# stm32f0driver1.net
KiCad netlist of a schematic drawn in EAGLE
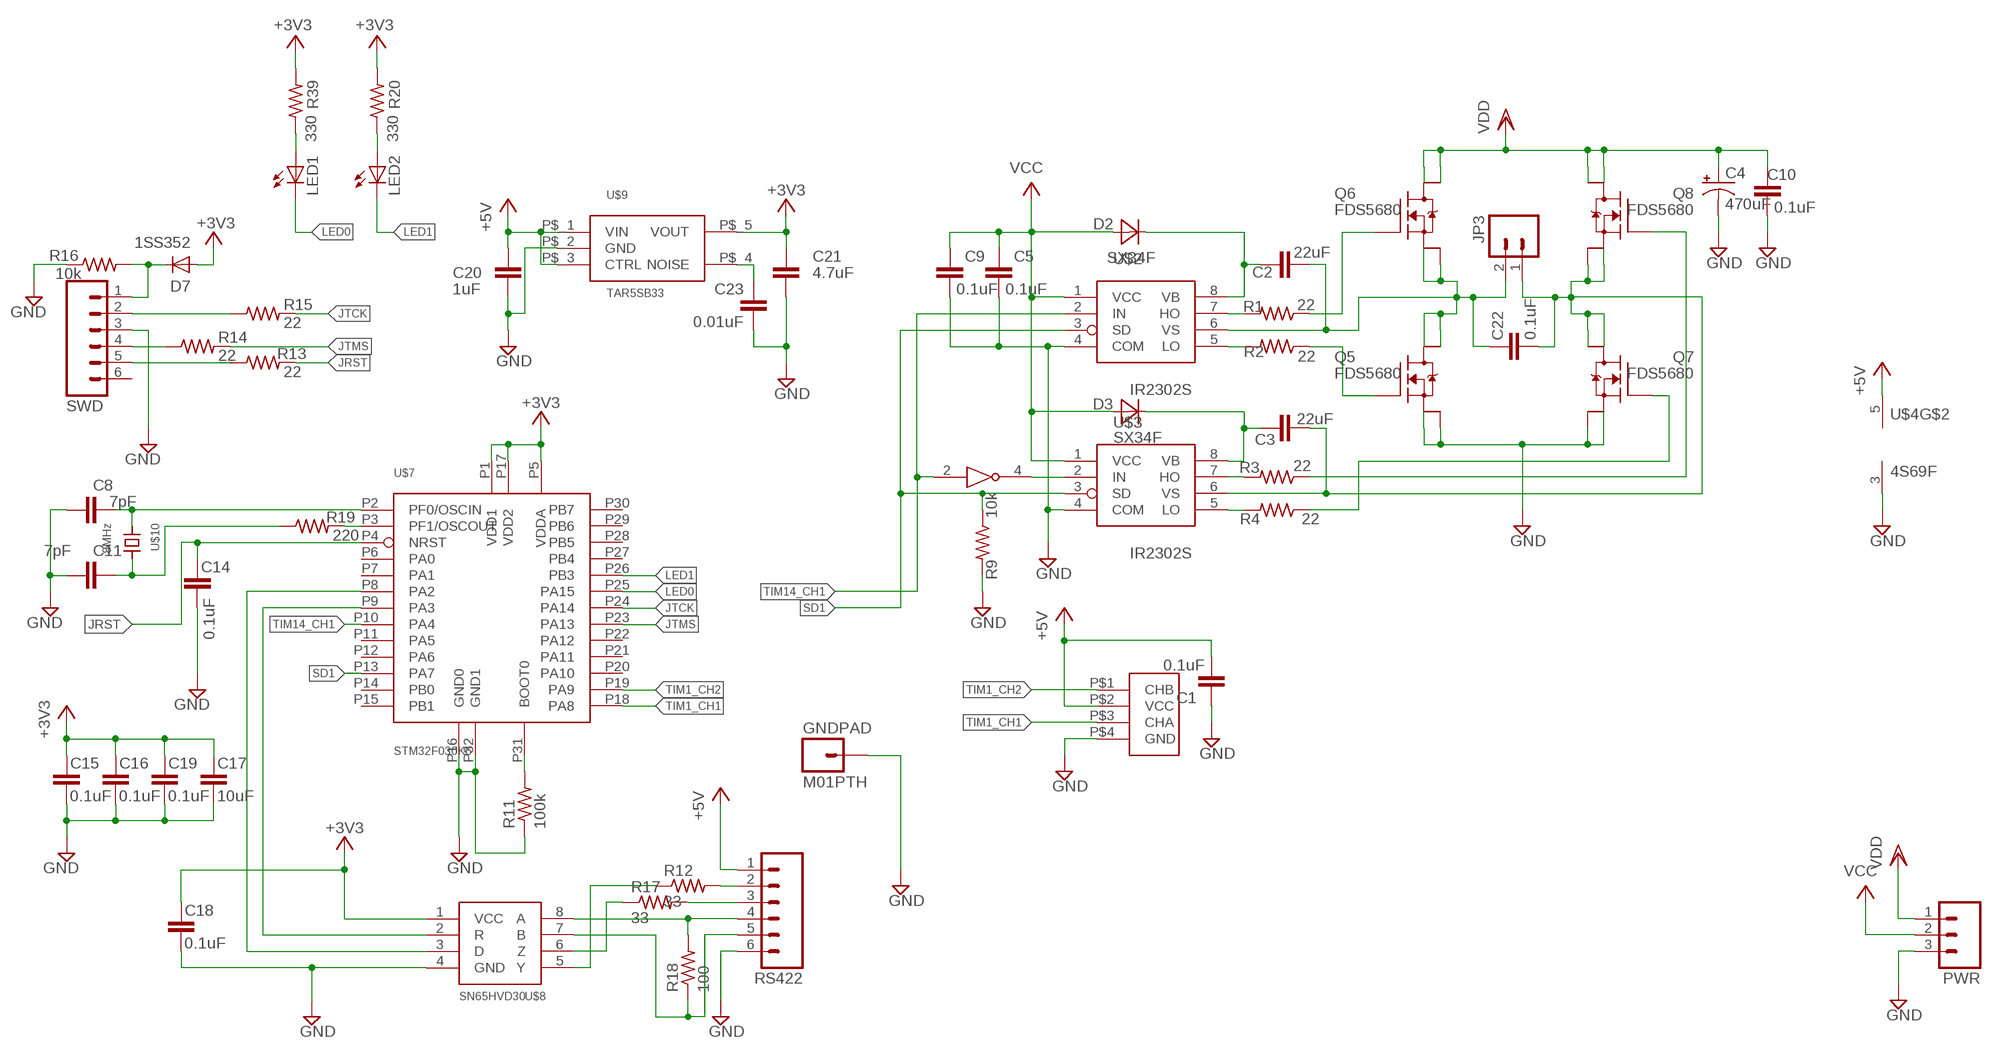
[diagram p0: schematic, sheet 1]

(export (version "E")
  (design (tool "Eeschema 10.0.6"))
  (components
    (comp (ref "C1")
      (value "0.1uF")
      (footprint "eagle-import:C0603")
      (libsource (lib "eagle-import") (part "C-EUC0603"))
    )
    (comp (ref "C2")
      (value "22uF")
      (footprint "eagle-import:C3225")
      (libsource (lib "eagle-import") (part "C-EUC3225"))
    )
    (comp (ref "C3")
      (value "22uF")
      (footprint "eagle-import:C3225")
      (libsource (lib "eagle-import") (part "C-EUC3225"))
    )
    (comp (ref "C4")
      (value "470uF")
      (footprint "eagle-import:E5-10,5")
      (libsource (lib "eagle-import") (part "CPOL-USE5-10.5"))
    )
    (comp (ref "C5")
      (value "0.1uF")
      (footprint "eagle-import:C0603")
      (libsource (lib "eagle-import") (part "C-EUC0603"))
    )
    (comp (ref "C8")
      (value "7pF")
      (footprint "eagle-import:C0603")
      (libsource (lib "eagle-import") (part "C-EUC0603"))
    )
    (comp (ref "C9")
      (value "0.1uF")
      (footprint "eagle-import:C0603")
      (libsource (lib "eagle-import") (part "C-EUC0603"))
    )
    (comp (ref "C10")
      (value "0.1uF")
      (footprint "eagle-import:C0603")
      (libsource (lib "eagle-import") (part "C-EUC0603"))
    )
    (comp (ref "C11")
      (value "7pF")
      (footprint "eagle-import:C0603")
      (libsource (lib "eagle-import") (part "C-EUC0603"))
    )
    (comp (ref "C14")
      (value "0.1uF")
      (footprint "eagle-import:C1608")
      (libsource (lib "eagle-import") (part "C-EUC1608"))
    )
    (comp (ref "C15")
      (value "0.1uF")
      (footprint "eagle-import:C1608")
      (libsource (lib "eagle-import") (part "C-EUC1608"))
    )
    (comp (ref "C16")
      (value "0.1uF")
      (footprint "eagle-import:C1608")
      (libsource (lib "eagle-import") (part "C-EUC1608"))
    )
    (comp (ref "C17")
      (value "10uF")
      (footprint "eagle-import:C3216")
      (libsource (lib "eagle-import") (part "C-EUC3216"))
    )
    (comp (ref "C18")
      (value "0.1uF")
      (footprint "eagle-import:C1608")
      (libsource (lib "eagle-import") (part "C-EUC1608"))
    )
    (comp (ref "C19")
      (value "0.1uF")
      (footprint "eagle-import:C1608")
      (libsource (lib "eagle-import") (part "C-EUC1608"))
    )
    (comp (ref "C20")
      (value "1uF")
      (footprint "eagle-import:C2012")
      (libsource (lib "eagle-import") (part "C-EUC2012"))
    )
    (comp (ref "C21")
      (value "4.7uF")
      (footprint "eagle-import:C2012")
      (libsource (lib "eagle-import") (part "C-EUC2012"))
    )
    (comp (ref "C22")
      (value "0.1uF")
      (footprint "eagle-import:C0603")
      (libsource (lib "eagle-import") (part "C-EUC0603"))
    )
    (comp (ref "C23")
      (value "0.01uF")
      (footprint "eagle-import:C0603")
      (libsource (lib "eagle-import") (part "C-EUC0603"))
    )
    (comp (ref "D2")
      (value "SX34F")
      (footprint "eagle-import:SMA")
      (libsource (lib "eagle-import") (part "MBRA340T3"))
    )
    (comp (ref "D3")
      (value "SX34F")
      (footprint "eagle-import:SMA")
      (libsource (lib "eagle-import") (part "MBRA340T3"))
    )
    (comp (ref "D7")
      (value "1SS352")
      (footprint "eagle-import:SOD-323")
      (libsource (lib "eagle-import") (part "DIODESOD"))
    )
    (comp (ref "GNDPAD")
      (value "M01PTH")
      (footprint "eagle-import:1X01")
      (libsource (lib "eagle-import") (part "M01PTH"))
    )
    (comp (ref "JP3")
      (value "M02PTH3")
      (footprint "eagle-import:1X02_LONGPADS")
      (libsource (lib "eagle-import") (part "M02PTH3"))
    )
    (comp (ref "LED1")
      (value "LED0603")
      (footprint "eagle-import:LED-0603")
      (libsource (lib "eagle-import") (part "LED0603"))
    )
    (comp (ref "LED2")
      (value "LED0603")
      (footprint "eagle-import:LED-0603")
      (libsource (lib "eagle-import") (part "LED0603"))
    )
    (comp (ref "PWR")
      (value "M03LONGPADS")
      (footprint "eagle-import:1X03_LONGPADS")
      (libsource (lib "eagle-import") (part "M03LONGPADS"))
    )
    (comp (ref "Q5")
      (value "FDS5680")
      (footprint "eagle-import:1206-8CHIP-FET")
      (libsource (lib "eagle-import") (part "FDS5680"))
    )
    (comp (ref "Q6")
      (value "FDS5680")
      (footprint "eagle-import:1206-8CHIP-FET")
      (libsource (lib "eagle-import") (part "FDS5680"))
    )
    (comp (ref "Q7")
      (value "FDS5680")
      (footprint "eagle-import:1206-8CHIP-FET")
      (libsource (lib "eagle-import") (part "FDS5680"))
    )
    (comp (ref "Q8")
      (value "FDS5680")
      (footprint "eagle-import:1206-8CHIP-FET")
      (libsource (lib "eagle-import") (part "FDS5680"))
    )
    (comp (ref "R1")
      (value "22")
      (footprint "eagle-import:R0603")
      (libsource (lib "eagle-import") (part "R-US_R0603"))
    )
    (comp (ref "R2")
      (value "22")
      (footprint "eagle-import:R0603")
      (libsource (lib "eagle-import") (part "R-US_R0603"))
    )
    (comp (ref "R3")
      (value "22")
      (footprint "eagle-import:R0603")
      (libsource (lib "eagle-import") (part "R-US_R0603"))
    )
    (comp (ref "R4")
      (value "22")
      (footprint "eagle-import:R0603")
      (libsource (lib "eagle-import") (part "R-US_R0603"))
    )
    (comp (ref "R9")
      (value "10k")
      (footprint "eagle-import:R0603")
      (libsource (lib "eagle-import") (part "R-US_R0603"))
    )
    (comp (ref "R11")
      (value "100k")
      (footprint "eagle-import:R0603")
      (libsource (lib "eagle-import") (part "R-US_R0603"))
    )
    (comp (ref "R12")
      (value "33")
      (footprint "eagle-import:R0603")
      (libsource (lib "eagle-import") (part "R-US_R0603"))
    )
    (comp (ref "R13")
      (value "22")
      (footprint "eagle-import:R0603")
      (libsource (lib "eagle-import") (part "R-US_R0603"))
    )
    (comp (ref "R14")
      (value "22")
      (footprint "eagle-import:R0603")
      (libsource (lib "eagle-import") (part "R-US_R0603"))
    )
    (comp (ref "R15")
      (value "22")
      (footprint "eagle-import:R0603")
      (libsource (lib "eagle-import") (part "R-US_R0603"))
    )
    (comp (ref "R16")
      (value "10k")
      (footprint "eagle-import:R0603")
      (libsource (lib "eagle-import") (part "R-US_R0603"))
    )
    (comp (ref "R17")
      (value "33")
      (footprint "eagle-import:R0603")
      (libsource (lib "eagle-import") (part "R-US_R0603"))
    )
    (comp (ref "R18")
      (value "100")
      (footprint "eagle-import:R0603")
      (libsource (lib "eagle-import") (part "R-US_R0603"))
    )
    (comp (ref "R19")
      (value "220")
      (footprint "eagle-import:R0603")
      (libsource (lib "eagle-import") (part "R-US_R0603"))
    )
    (comp (ref "R20")
      (value "330")
      (footprint "eagle-import:R0603")
      (libsource (lib "eagle-import") (part "R-US_R0603"))
    )
    (comp (ref "R39")
      (value "330")
      (footprint "eagle-import:R0603")
      (libsource (lib "eagle-import") (part "R-US_R0603"))
    )
    (comp (ref "RS422")
      (value "M06SIP")
      (footprint "eagle-import:1X06")
      (libsource (lib "eagle-import") (part "M06SIP"))
    )
    (comp (ref "SWD")
      (value "M06SIP")
      (footprint "eagle-import:1X06")
      (libsource (lib "eagle-import") (part "M06SIP"))
    )
    (comp (ref "U$1")
      (value "HEDS9701-C54")
      (footprint "eagle-import:HEDS9701")
      (libsource (lib "eagle-import") (part "HEDS9701-C54"))
    )
    (comp (ref "U$2")
      (value "IR2302S")
      (footprint "eagle-import:SO8")
      (libsource (lib "eagle-import") (part "IR2302S"))
    )
    (comp (ref "U$3")
      (value "IR2302S")
      (footprint "eagle-import:SO8")
      (libsource (lib "eagle-import") (part "IR2302S"))
    )
    (comp (ref "U$4")
      (value "4S69F")
      (footprint "eagle-import:SOT23-5")
      (libsource (lib "eagle-import") (part "4S69F"))
    )
    (comp (ref "U$7")
      (value "STM32F030K6")
      (footprint "eagle-import:LQFP32")
      (libsource (lib "eagle-import") (part "STM32F030K6"))
    )
    (comp (ref "U$8")
      (value "SN65HVD30")
      (footprint "eagle-import:SO8")
      (libsource (lib "eagle-import") (part "SN65HVD30"))
    )
    (comp (ref "U$9")
      (value "TAR5SB33")
      (footprint "eagle-import:TAR5SB33")
      (libsource (lib "eagle-import") (part "TAR5SB33"))
    )
    (comp (ref "U$10")
      (value "8MHz")
      (footprint "eagle-import:SMD5032")
      (libsource (lib "eagle-import") (part "NX5032GA"))
    )
  )
  (nets
    (net (code "1") (name "+3V3") (class "Default")
      (node (ref "C15") (pin "1") (pinfunction "1_1") (pintype "passive"))
      (node (ref "C16") (pin "1") (pinfunction "1_1") (pintype "passive"))
      (node (ref "C17") (pin "1") (pinfunction "1_1") (pintype "passive"))
      (node (ref "C18") (pin "1") (pinfunction "1_1") (pintype "passive"))
      (node (ref "C19") (pin "1") (pinfunction "1_1") (pintype "passive"))
      (node (ref "C21") (pin "1") (pinfunction "1_1") (pintype "passive"))
      (node (ref "D7") (pin "2") (pinfunction "A_2") (pintype "passive"))
      (node (ref "R20") (pin "2") (pinfunction "2_2") (pintype "passive"))
      (node (ref "R39") (pin "2") (pinfunction "2_2") (pintype "passive"))
      (node (ref "U$7") (pin "P1") (pinfunction "VDD1_P1") (pintype "power_in"))
      (node (ref "U$7") (pin "P17") (pinfunction "VDD2_P17") (pintype "bidirectional"))
      (node (ref "U$7") (pin "P5") (pinfunction "VDDA_P5") (pintype "power_in"))
      (node (ref "U$8") (pin "1") (pinfunction "VCC_1") (pintype "power_in"))
      (node (ref "U$9") (pin "P$_5") (pinfunction "VOUT_P$_5") (pintype "power_in"))
    )
    (net (code "2") (name "+5V") (class "Default")
      (node (ref "C1") (pin "2") (pinfunction "2_2") (pintype "passive"))
      (node (ref "C20") (pin "1") (pinfunction "1_1") (pintype "passive"))
      (node (ref "RS422") (pin "1") (pinfunction "1_1") (pintype "passive"))
      (node (ref "U$1") (pin "P$2") (pinfunction "VCC_P$2") (pintype "power_in"))
      (node (ref "U$4") (pin "5") (pinfunction "V+_5") (pintype "power_in"))
      (node (ref "U$9") (pin "P$_1") (pinfunction "VIN_P$_1") (pintype "power_in"))
      (node (ref "U$9") (pin "P$_3") (pinfunction "CTRL_P$_3") (pintype "input"))
    )
    (net (code "3") (name "GND") (class "Default")
      (node (ref "C1") (pin "1") (pinfunction "1_1") (pintype "passive"))
      (node (ref "C10") (pin "2") (pinfunction "2_2") (pintype "passive"))
      (node (ref "C11") (pin "2") (pinfunction "2_2") (pintype "passive"))
      (node (ref "C14") (pin "2") (pinfunction "2_2") (pintype "passive"))
      (node (ref "C15") (pin "2") (pinfunction "2_2") (pintype "passive"))
      (node (ref "C16") (pin "2") (pinfunction "2_2") (pintype "passive"))
      (node (ref "C17") (pin "2") (pinfunction "2_2") (pintype "passive"))
      (node (ref "C18") (pin "2") (pinfunction "2_2") (pintype "passive"))
      (node (ref "C19") (pin "2") (pinfunction "2_2") (pintype "passive"))
      (node (ref "C20") (pin "2") (pinfunction "2_2") (pintype "passive"))
      (node (ref "C21") (pin "2") (pinfunction "2_2") (pintype "passive"))
      (node (ref "C23") (pin "2") (pinfunction "2_2") (pintype "passive"))
      (node (ref "C4") (pin "-") (pinfunction "-_-") (pintype "passive"))
      (node (ref "C5") (pin "2") (pinfunction "2_2") (pintype "passive"))
      (node (ref "C8") (pin "2") (pinfunction "2_2") (pintype "passive"))
      (node (ref "C9") (pin "2") (pinfunction "2_2") (pintype "passive"))
      (node (ref "GNDPAD") (pin "1") (pinfunction "1_1") (pintype "passive"))
      (node (ref "PWR") (pin "3") (pinfunction "3_3") (pintype "passive"))
      (node (ref "Q5") (pin "1") (pinfunction "S_1") (pintype "passive"))
      (node (ref "Q5") (pin "2") (pinfunction "S1_2") (pintype "passive"))
      (node (ref "Q5") (pin "3") (pinfunction "S2_3") (pintype "passive"))
      (node (ref "Q7") (pin "1") (pinfunction "S_1") (pintype "passive"))
      (node (ref "Q7") (pin "2") (pinfunction "S1_2") (pintype "passive"))
      (node (ref "Q7") (pin "3") (pinfunction "S2_3") (pintype "passive"))
      (node (ref "R11") (pin "1") (pinfunction "1_1") (pintype "passive"))
      (node (ref "R16") (pin "1") (pinfunction "1_1") (pintype "passive"))
      (node (ref "R9") (pin "2") (pinfunction "2_2") (pintype "passive"))
      (node (ref "RS422") (pin "6") (pinfunction "6_6") (pintype "passive"))
      (node (ref "SWD") (pin "3") (pinfunction "3_3") (pintype "passive"))
      (node (ref "U$1") (pin "P$4") (pinfunction "GND_P$4") (pintype "power_in"))
      (node (ref "U$2") (pin "4") (pinfunction "COM_4") (pintype "power_in"))
      (node (ref "U$3") (pin "4") (pinfunction "COM_4") (pintype "power_in"))
      (node (ref "U$4") (pin "3") (pinfunction "V-_3") (pintype "power_in"))
      (node (ref "U$7") (pin "P16") (pinfunction "GND0_P16") (pintype "power_in"))
      (node (ref "U$7") (pin "P32") (pinfunction "GND1_P32") (pintype "bidirectional"))
      (node (ref "U$8") (pin "4") (pinfunction "GND_4") (pintype "power_in"))
      (node (ref "U$9") (pin "P$_2") (pinfunction "GND_P$_2") (pintype "power_in"))
    )
    (net (code "4") (name "JRST") (class "Default")
      (node (ref "C14") (pin "1") (pinfunction "1_1") (pintype "passive"))
      (node (ref "R13") (pin "2") (pinfunction "2_2") (pintype "passive"))
      (node (ref "U$7") (pin "P4") (pinfunction "NRST_P4") (pintype "input"))
    )
    (net (code "5") (name "JTCK") (class "Default")
      (node (ref "R15") (pin "2") (pinfunction "2_2") (pintype "passive"))
      (node (ref "U$7") (pin "P24") (pinfunction "PA14_P24") (pintype "bidirectional"))
    )
    (net (code "6") (name "JTMS") (class "Default")
      (node (ref "R14") (pin "2") (pinfunction "2_2") (pintype "passive"))
      (node (ref "U$7") (pin "P23") (pinfunction "PA13_P23") (pintype "bidirectional"))
    )
    (net (code "7") (name "LED0") (class "Default")
      (node (ref "LED1") (pin "C") (pinfunction "C_C") (pintype "passive"))
      (node (ref "U$7") (pin "P25") (pinfunction "PA15_P25") (pintype "bidirectional"))
    )
    (net (code "8") (name "LED1") (class "Default")
      (node (ref "LED2") (pin "C") (pinfunction "C_C") (pintype "passive"))
      (node (ref "U$7") (pin "P26") (pinfunction "PB3_P26") (pintype "bidirectional"))
    )
    (net (code "9") (name "Net-(D7-C)") (class "Default")
      (node (ref "D7") (pin "1") (pinfunction "C_1") (pintype "passive"))
      (node (ref "R16") (pin "2") (pinfunction "2_2") (pintype "passive"))
      (node (ref "SWD") (pin "1") (pinfunction "1_1") (pintype "passive"))
    )
    (net (code "10") (name "Net-(LED1-PadA)") (class "Default")
      (node (ref "LED1") (pin "A") (pinfunction "A_A") (pintype "passive"))
      (node (ref "R39") (pin "1") (pinfunction "1_1") (pintype "passive"))
    )
    (net (code "11") (name "Net-(LED2-PadA)") (class "Default")
      (node (ref "LED2") (pin "A") (pinfunction "A_A") (pintype "passive"))
      (node (ref "R20") (pin "1") (pinfunction "1_1") (pintype "passive"))
    )
    (net (code "12") (name "Net-(Q5-D)") (class "Default")
      (node (ref "C2") (pin "2") (pinfunction "2_2") (pintype "passive"))
      (node (ref "C22") (pin "1") (pinfunction "1_1") (pintype "passive"))
      (node (ref "JP3") (pin "2") (pinfunction "2_2") (pintype "passive"))
      (node (ref "Q5") (pin "5") (pinfunction "D_5") (pintype "passive"))
      (node (ref "Q5") (pin "6") (pinfunction "D1_6") (pintype "passive"))
      (node (ref "Q5") (pin "7") (pinfunction "D2_7") (pintype "passive"))
      (node (ref "Q5") (pin "8") (pinfunction "D3_8") (pintype "passive"))
      (node (ref "Q6") (pin "1") (pinfunction "S_1") (pintype "passive"))
      (node (ref "Q6") (pin "2") (pinfunction "S1_2") (pintype "passive"))
      (node (ref "Q6") (pin "3") (pinfunction "S2_3") (pintype "passive"))
      (node (ref "U$2") (pin "6") (pinfunction "VS_6") (pintype "bidirectional"))
    )
    (net (code "13") (name "Net-(Q5-G)") (class "Default")
      (node (ref "Q5") (pin "4") (pinfunction "G_4") (pintype "passive"))
      (node (ref "R2") (pin "1") (pinfunction "1_1") (pintype "passive"))
    )
    (net (code "14") (name "Net-(Q6-G)") (class "Default")
      (node (ref "Q6") (pin "4") (pinfunction "G_4") (pintype "passive"))
      (node (ref "R1") (pin "1") (pinfunction "1_1") (pintype "passive"))
    )
    (net (code "15") (name "Net-(Q7-D)") (class "Default")
      (node (ref "C22") (pin "2") (pinfunction "2_2") (pintype "passive"))
      (node (ref "C3") (pin "2") (pinfunction "2_2") (pintype "passive"))
      (node (ref "JP3") (pin "1") (pinfunction "1_1") (pintype "passive"))
      (node (ref "Q7") (pin "5") (pinfunction "D_5") (pintype "passive"))
      (node (ref "Q7") (pin "6") (pinfunction "D1_6") (pintype "passive"))
      (node (ref "Q7") (pin "7") (pinfunction "D2_7") (pintype "passive"))
      (node (ref "Q7") (pin "8") (pinfunction "D3_8") (pintype "passive"))
      (node (ref "Q8") (pin "1") (pinfunction "S_1") (pintype "passive"))
      (node (ref "Q8") (pin "2") (pinfunction "S1_2") (pintype "passive"))
      (node (ref "Q8") (pin "3") (pinfunction "S2_3") (pintype "passive"))
      (node (ref "U$3") (pin "6") (pinfunction "VS_6") (pintype "bidirectional"))
    )
    (net (code "16") (name "Net-(Q7-G)") (class "Default")
      (node (ref "Q7") (pin "4") (pinfunction "G_4") (pintype "passive"))
      (node (ref "R4") (pin "1") (pinfunction "1_1") (pintype "passive"))
    )
    (net (code "17") (name "Net-(Q8-G)") (class "Default")
      (node (ref "Q8") (pin "4") (pinfunction "G_4") (pintype "passive"))
      (node (ref "R3") (pin "1") (pinfunction "1_1") (pintype "passive"))
    )
    (net (code "18") (name "Net-(R12-Pad2)") (class "Default")
      (node (ref "R12") (pin "2") (pinfunction "2_2") (pintype "passive"))
      (node (ref "RS422") (pin "2") (pinfunction "2_2") (pintype "passive"))
    )
    (net (code "19") (name "Net-(R13-Pad1)") (class "Default")
      (node (ref "R13") (pin "1") (pinfunction "1_1") (pintype "passive"))
      (node (ref "SWD") (pin "5") (pinfunction "5_5") (pintype "passive"))
    )
    (net (code "20") (name "Net-(R14-Pad1)") (class "Default")
      (node (ref "R14") (pin "1") (pinfunction "1_1") (pintype "passive"))
      (node (ref "SWD") (pin "4") (pinfunction "4_4") (pintype "passive"))
    )
    (net (code "21") (name "Net-(R15-Pad1)") (class "Default")
      (node (ref "R15") (pin "1") (pinfunction "1_1") (pintype "passive"))
      (node (ref "SWD") (pin "2") (pinfunction "2_2") (pintype "passive"))
    )
    (net (code "22") (name "Net-(R17-Pad2)") (class "Default")
      (node (ref "R17") (pin "2") (pinfunction "2_2") (pintype "passive"))
      (node (ref "RS422") (pin "3") (pinfunction "3_3") (pintype "passive"))
    )
    (net (code "23") (name "Net-(U$2-HO)") (class "Default")
      (node (ref "R1") (pin "2") (pinfunction "2_2") (pintype "passive"))
      (node (ref "U$2") (pin "7") (pinfunction "HO_7") (pintype "output"))
    )
    (net (code "24") (name "Net-(U$2-LO)") (class "Default")
      (node (ref "R2") (pin "2") (pinfunction "2_2") (pintype "passive"))
      (node (ref "U$2") (pin "5") (pinfunction "LO_5") (pintype "output"))
    )
    (net (code "25") (name "Net-(U$2-VB)") (class "Default")
      (node (ref "C2") (pin "1") (pinfunction "1_1") (pintype "passive"))
      (node (ref "D2") (pin "C") (pinfunction "C_C") (pintype "passive"))
      (node (ref "U$2") (pin "8") (pinfunction "VB_8") (pintype "bidirectional"))
    )
    (net (code "26") (name "Net-(U$3-HO)") (class "Default")
      (node (ref "R3") (pin "2") (pinfunction "2_2") (pintype "passive"))
      (node (ref "U$3") (pin "7") (pinfunction "HO_7") (pintype "output"))
    )
    (net (code "27") (name "Net-(U$3-IN)") (class "Default")
      (node (ref "U$3") (pin "2") (pinfunction "IN_2") (pintype "input"))
      (node (ref "U$4") (pin "4") (pinfunction "P$2_4") (pintype "bidirectional"))
    )
    (net (code "28") (name "Net-(U$3-LO)") (class "Default")
      (node (ref "R4") (pin "2") (pinfunction "2_2") (pintype "passive"))
      (node (ref "U$3") (pin "5") (pinfunction "LO_5") (pintype "output"))
    )
    (net (code "29") (name "Net-(U$3-VB)") (class "Default")
      (node (ref "C3") (pin "1") (pinfunction "1_1") (pintype "passive"))
      (node (ref "D3") (pin "C") (pinfunction "C_C") (pintype "passive"))
      (node (ref "U$3") (pin "8") (pinfunction "VB_8") (pintype "bidirectional"))
    )
    (net (code "30") (name "Net-(U$7-BOOT0)") (class "Default")
      (node (ref "R11") (pin "2") (pinfunction "2_2") (pintype "passive"))
      (node (ref "U$7") (pin "P31") (pinfunction "BOOT0_P31") (pintype "bidirectional"))
    )
    (net (code "31") (name "Net-(U$7-PA2)") (class "Default")
      (node (ref "U$7") (pin "P8") (pinfunction "PA2_P8") (pintype "bidirectional"))
      (node (ref "U$8") (pin "3") (pinfunction "D_3") (pintype "input"))
    )
    (net (code "32") (name "Net-(U$7-PA3)") (class "Default")
      (node (ref "U$7") (pin "P9") (pinfunction "PA3_P9") (pintype "bidirectional"))
      (node (ref "U$8") (pin "2") (pinfunction "R_2") (pintype "output"))
    )
    (net (code "33") (name "Net-(U$7-PF1{slash}OSCOUT)") (class "Default")
      (node (ref "R19") (pin "2") (pinfunction "2_2") (pintype "passive"))
      (node (ref "U$7") (pin "P3") (pinfunction "PF1/OSCOUT_P3") (pintype "bidirectional"))
    )
    (net (code "34") (name "Net-(U$8-A)") (class "Default")
      (node (ref "R18") (pin "2") (pinfunction "2_2") (pintype "passive"))
      (node (ref "RS422") (pin "4") (pinfunction "4_4") (pintype "passive"))
      (node (ref "U$8") (pin "8") (pinfunction "A_8") (pintype "input"))
    )
    (net (code "35") (name "Net-(U$8-B)") (class "Default")
      (node (ref "R18") (pin "1") (pinfunction "1_1") (pintype "passive"))
      (node (ref "RS422") (pin "5") (pinfunction "5_5") (pintype "passive"))
      (node (ref "U$8") (pin "7") (pinfunction "B_7") (pintype "input"))
    )
    (net (code "36") (name "Net-(U$8-Y)") (class "Default")
      (node (ref "R12") (pin "1") (pinfunction "1_1") (pintype "passive"))
      (node (ref "U$8") (pin "5") (pinfunction "Y_5") (pintype "output"))
    )
    (net (code "37") (name "Net-(U$8-Z)") (class "Default")
      (node (ref "R17") (pin "1") (pinfunction "1_1") (pintype "passive"))
      (node (ref "U$8") (pin "6") (pinfunction "Z_6") (pintype "output"))
    )
    (net (code "38") (name "Net-(U$9-NOISE)") (class "Default")
      (node (ref "C23") (pin "1") (pinfunction "1_1") (pintype "passive"))
      (node (ref "U$9") (pin "P$_4") (pinfunction "NOISE_P$_4") (pintype "input"))
    )
    (net (code "39") (name "Net-(U$10-P$1)") (class "Default")
      (node (ref "C8") (pin "1") (pinfunction "1_1") (pintype "passive"))
      (node (ref "U$10") (pin "P1") (pinfunction "P$1_P1") (pintype "bidirectional"))
      (node (ref "U$7") (pin "P2") (pinfunction "PF0/OSCIN_P2") (pintype "bidirectional"))
    )
    (net (code "40") (name "Net-(U$10-P$2)") (class "Default")
      (node (ref "C11") (pin "1") (pinfunction "1_1") (pintype "passive"))
      (node (ref "R19") (pin "1") (pinfunction "1_1") (pintype "passive"))
      (node (ref "U$10") (pin "P2") (pinfunction "P$2_P2") (pintype "bidirectional"))
    )
    (net (code "41") (name "SD1") (class "Default")
      (node (ref "R9") (pin "1") (pinfunction "1_1") (pintype "passive"))
      (node (ref "U$2") (pin "3") (pinfunction "SD_3") (pintype "input"))
      (node (ref "U$3") (pin "3") (pinfunction "SD_3") (pintype "input"))
      (node (ref "U$7") (pin "P13") (pinfunction "PA7_P13") (pintype "bidirectional"))
    )
    (net (code "42") (name "TIM1_CH1") (class "Default")
      (node (ref "U$1") (pin "P$3") (pinfunction "CHA_P$3") (pintype "output"))
      (node (ref "U$7") (pin "P18") (pinfunction "PA8_P18") (pintype "bidirectional"))
    )
    (net (code "43") (name "TIM1_CH2") (class "Default")
      (node (ref "U$1") (pin "P$1") (pinfunction "CHB_P$1") (pintype "output"))
      (node (ref "U$7") (pin "P19") (pinfunction "PA9_P19") (pintype "bidirectional"))
    )
    (net (code "44") (name "TIM14_CH1") (class "Default")
      (node (ref "U$2") (pin "2") (pinfunction "IN_2") (pintype "input"))
      (node (ref "U$4") (pin "2") (pinfunction "P$1_2") (pintype "bidirectional"))
      (node (ref "U$7") (pin "P10") (pinfunction "PA4_P10") (pintype "bidirectional"))
    )
    (net (code "45") (name "VCC") (class "Default")
      (node (ref "C5") (pin "1") (pinfunction "1_1") (pintype "passive"))
      (node (ref "C9") (pin "1") (pinfunction "1_1") (pintype "passive"))
      (node (ref "D2") (pin "A") (pinfunction "A_A") (pintype "passive"))
      (node (ref "D3") (pin "A") (pinfunction "A_A") (pintype "passive"))
      (node (ref "PWR") (pin "2") (pinfunction "2_2") (pintype "passive"))
      (node (ref "U$2") (pin "1") (pinfunction "VCC_1") (pintype "power_in"))
      (node (ref "U$3") (pin "1") (pinfunction "VCC_1") (pintype "power_in"))
    )
    (net (code "46") (name "VDD") (class "Default")
      (node (ref "C10") (pin "1") (pinfunction "1_1") (pintype "passive"))
      (node (ref "C4") (pin "+") (pinfunction "+_+") (pintype "passive"))
      (node (ref "PWR") (pin "1") (pinfunction "1_1") (pintype "passive"))
      (node (ref "Q6") (pin "5") (pinfunction "D_5") (pintype "passive"))
      (node (ref "Q6") (pin "6") (pinfunction "D1_6") (pintype "passive"))
      (node (ref "Q6") (pin "7") (pinfunction "D2_7") (pintype "passive"))
      (node (ref "Q6") (pin "8") (pinfunction "D3_8") (pintype "passive"))
      (node (ref "Q8") (pin "5") (pinfunction "D_5") (pintype "passive"))
      (node (ref "Q8") (pin "6") (pinfunction "D1_6") (pintype "passive"))
      (node (ref "Q8") (pin "7") (pinfunction "D2_7") (pintype "passive"))
      (node (ref "Q8") (pin "8") (pinfunction "D3_8") (pintype "passive"))
    )
    (net (code "47") (name "unconnected-(SWD-Pad6)") (class "Default")
      (node (ref "SWD") (pin "6") (pinfunction "6_6") (pintype "passive"))
    )
    (net (code "48") (name "unconnected-(U$7-PA0-PadP6)") (class "Default")
      (node (ref "U$7") (pin "P6") (pinfunction "PA0_P6") (pintype "bidirectional"))
    )
    (net (code "49") (name "unconnected-(U$7-PA1-PadP7)") (class "Default")
      (node (ref "U$7") (pin "P7") (pinfunction "PA1_P7") (pintype "bidirectional"))
    )
    (net (code "50") (name "unconnected-(U$7-PA5-PadP11)") (class "Default")
      (node (ref "U$7") (pin "P11") (pinfunction "PA5_P11") (pintype "bidirectional"))
    )
    (net (code "51") (name "unconnected-(U$7-PA6-PadP12)") (class "Default")
      (node (ref "U$7") (pin "P12") (pinfunction "PA6_P12") (pintype "bidirectional"))
    )
    (net (code "52") (name "unconnected-(U$7-PA10-PadP20)") (class "Default")
      (node (ref "U$7") (pin "P20") (pinfunction "PA10_P20") (pintype "bidirectional"))
    )
    (net (code "53") (name "unconnected-(U$7-PA11-PadP21)") (class "Default")
      (node (ref "U$7") (pin "P21") (pinfunction "PA11_P21") (pintype "bidirectional"))
    )
    (net (code "54") (name "unconnected-(U$7-PA12-PadP22)") (class "Default")
      (node (ref "U$7") (pin "P22") (pinfunction "PA12_P22") (pintype "bidirectional"))
    )
    (net (code "55") (name "unconnected-(U$7-PB0-PadP14)") (class "Default")
      (node (ref "U$7") (pin "P14") (pinfunction "PB0_P14") (pintype "bidirectional"))
    )
    (net (code "56") (name "unconnected-(U$7-PB1-PadP15)") (class "Default")
      (node (ref "U$7") (pin "P15") (pinfunction "PB1_P15") (pintype "bidirectional"))
    )
    (net (code "57") (name "unconnected-(U$7-PB4-PadP27)") (class "Default")
      (node (ref "U$7") (pin "P27") (pinfunction "PB4_P27") (pintype "bidirectional"))
    )
    (net (code "58") (name "unconnected-(U$7-PB5-PadP28)") (class "Default")
      (node (ref "U$7") (pin "P28") (pinfunction "PB5_P28") (pintype "bidirectional"))
    )
    (net (code "59") (name "unconnected-(U$7-PB6-PadP29)") (class "Default")
      (node (ref "U$7") (pin "P29") (pinfunction "PB6_P29") (pintype "bidirectional"))
    )
    (net (code "60") (name "unconnected-(U$7-PB7-PadP30)") (class "Default")
      (node (ref "U$7") (pin "P30") (pinfunction "PB7_P30") (pintype "bidirectional"))
    )
  )
)
